# Connections.net
KiCad netlist of a schematic drawn in Altium Designer
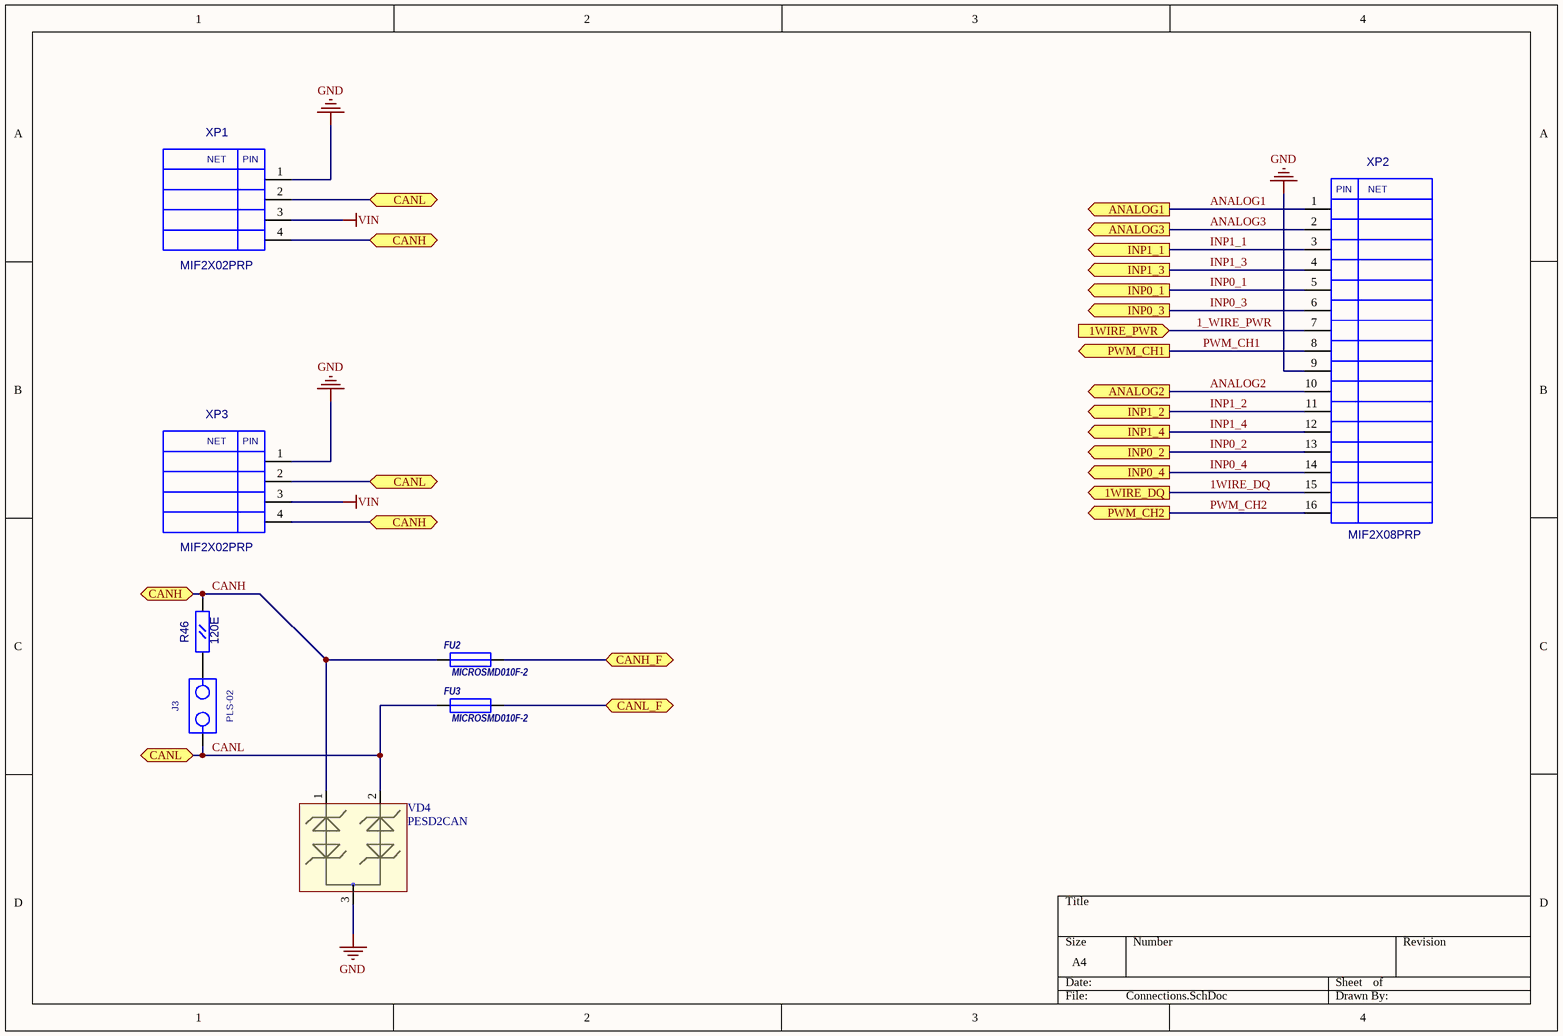
[diagram p0: Connections.SchDoc]

(export (version "E")
  (design (tool "Eeschema 10.0.6"))
  (components
    (comp (ref "FU2")
      (value "MICROSMD010F-2")
      (footprint "RC1210")
      (description "MICROSMD")
      (libsource (lib "gprs_modem_2") (part "MICROSMD"))
    )
    (comp (ref "FU3")
      (value "MICROSMD010F-2")
      (footprint "RC1210")
      (description "MICROSMD")
      (libsource (lib "gprs_modem_2") (part "MICROSMD"))
    )
    (comp (ref "J3") (value "PLS-02") (footprint "PLS-02") (libsource (lib "gprs_modem_2") (part "PLS-02")))
    (comp (ref "R46")
      (value "120E")
      (footprint "RC0805")
      (description "RC0805")
      (libsource (lib "gprs_modem_2") (part "RC0805"))
    )
    (comp (ref "VD4")
      (value "PESD2CAN")
      (footprint "SOT-23(123)")
      (description "TVS for CAN")
      (libsource (lib "gprs_modem_2") (part "PESD2CAN"))
    )
    (comp (ref "XP1")
      (value "MIF2X02PRP")
      (footprint "MIF2X02PRP")
      (libsource (lib "gprs_modem_2") (part "MIF2X02PRP"))
    )
    (comp (ref "XP2")
      (value "MIF2X08PRP")
      (footprint "MIF2X08PRP")
      (libsource (lib "gprs_modem_2") (part "MIF2X08PRP"))
    )
    (comp (ref "XP3")
      (value "MIF2X02PRP")
      (footprint "MIF2X02PRP")
      (libsource (lib "gprs_modem_2") (part "MIF2X02PRP"))
    )
  )
  (nets
    (net (code "1") (name "/1WIRE_DQ") (class "Default")
      (node (ref "XP2") (pin "15") (pinfunction "15_15") (pintype "passive"))
    )
    (net (code "2") (name "/1_WIRE_PWR") (class "Default")
      (node (ref "XP2") (pin "7") (pinfunction "7_7") (pintype "passive"))
    )
    (net (code "3") (name "/ANALOG1") (class "Default")
      (node (ref "XP2") (pin "1") (pinfunction "1_1") (pintype "passive"))
    )
    (net (code "4") (name "/ANALOG2") (class "Default")
      (node (ref "XP2") (pin "10") (pinfunction "10_10") (pintype "passive"))
    )
    (net (code "5") (name "/ANALOG3") (class "Default")
      (node (ref "XP2") (pin "2") (pinfunction "2_2") (pintype "passive"))
    )
    (net (code "6") (name "/CANH") (class "Default")
      (node (ref "FU2") (pin "1") (pintype "passive"))
      (node (ref "R46") (pin "2") (pinfunction "B_2") (pintype "passive"))
      (node (ref "VD4") (pin "1") (pinfunction "1_1") (pintype "passive"))
      (node (ref "XP1") (pin "4") (pinfunction "4_4") (pintype "passive"))
      (node (ref "XP3") (pin "4") (pinfunction "4_4") (pintype "passive"))
    )
    (net (code "7") (name "/CANH_F") (class "Default") (node (ref "FU2") (pin "2") (pintype "passive")))
    (net (code "8") (name "/CANL") (class "Default")
      (node (ref "FU3") (pin "1") (pintype "passive"))
      (node (ref "J3") (pin "1") (pintype "passive"))
      (node (ref "VD4") (pin "2") (pinfunction "2_2") (pintype "passive"))
      (node (ref "XP1") (pin "2") (pinfunction "2_2") (pintype "passive"))
      (node (ref "XP3") (pin "2") (pinfunction "2_2") (pintype "passive"))
    )
    (net (code "9") (name "/CANL_F") (class "Default") (node (ref "FU3") (pin "2") (pintype "passive")))
    (net (code "10") (name "/INP0_1") (class "Default")
      (node (ref "XP2") (pin "5") (pinfunction "5_5") (pintype "passive"))
    )
    (net (code "11") (name "/INP0_2") (class "Default")
      (node (ref "XP2") (pin "13") (pinfunction "13_13") (pintype "passive"))
    )
    (net (code "12") (name "/INP0_3") (class "Default")
      (node (ref "XP2") (pin "6") (pinfunction "6_6") (pintype "passive"))
    )
    (net (code "13") (name "/INP0_4") (class "Default")
      (node (ref "XP2") (pin "14") (pinfunction "14_14") (pintype "passive"))
    )
    (net (code "14") (name "/INP1_1") (class "Default")
      (node (ref "XP2") (pin "3") (pinfunction "3_3") (pintype "passive"))
    )
    (net (code "15") (name "/INP1_2") (class "Default")
      (node (ref "XP2") (pin "11") (pinfunction "11_11") (pintype "passive"))
    )
    (net (code "16") (name "/INP1_3") (class "Default")
      (node (ref "XP2") (pin "4") (pinfunction "4_4") (pintype "passive"))
    )
    (net (code "17") (name "/INP1_4") (class "Default")
      (node (ref "XP2") (pin "12") (pinfunction "12_12") (pintype "passive"))
    )
    (net (code "18") (name "/PWM_CH1") (class "Default")
      (node (ref "XP2") (pin "8") (pinfunction "8_8") (pintype "passive"))
    )
    (net (code "19") (name "/PWM_CH2") (class "Default")
      (node (ref "XP2") (pin "16") (pinfunction "16_16") (pintype "passive"))
    )
    (net (code "20") (name "GND") (class "Default")
      (node (ref "VD4") (pin "3") (pinfunction "3_3") (pintype "passive"))
      (node (ref "XP1") (pin "1") (pinfunction "1_1") (pintype "passive"))
      (node (ref "XP2") (pin "9") (pinfunction "9_9") (pintype "passive"))
      (node (ref "XP3") (pin "1") (pinfunction "1_1") (pintype "passive"))
    )
    (net (code "21") (name "Net-(R46-A)") (class "Default")
      (node (ref "J3") (pin "2") (pintype "passive"))
      (node (ref "R46") (pin "1") (pinfunction "A_1") (pintype "passive"))
    )
    (net (code "22") (name "VIN") (class "Default")
      (node (ref "XP1") (pin "3") (pinfunction "3_3") (pintype "passive"))
      (node (ref "XP3") (pin "3") (pinfunction "3_3") (pintype "passive"))
    )
  )
)
